# wireless-dong-mk-2_2.net
KiCad netlist of a schematic drawn in EAGLE
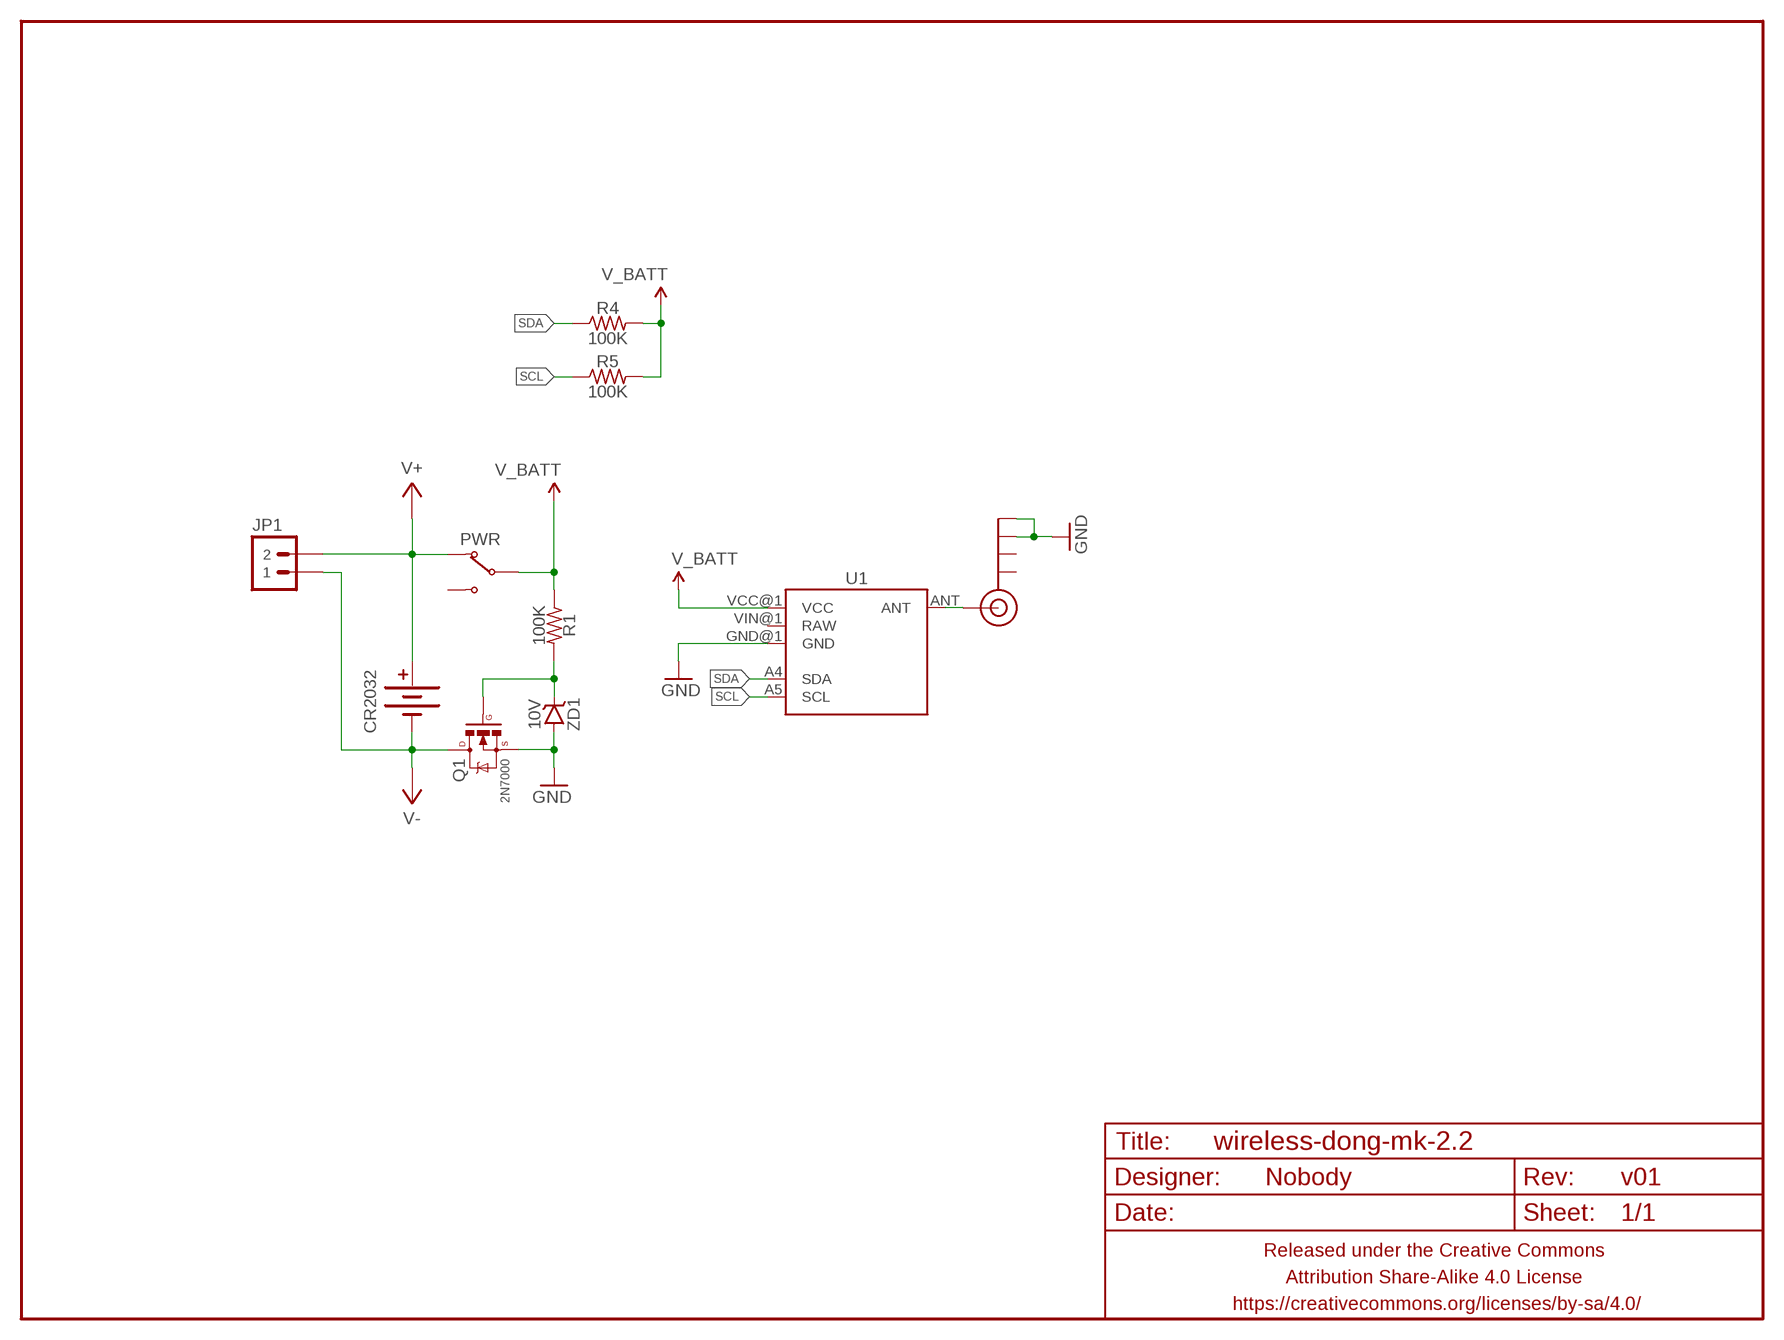
[diagram p0: schematic, sheet 1]

(export (version "E")
  (design (tool "Eeschema 10.0.6"))
  (components
    (comp (ref "ANT")
      (value "SMA_EDGE")
      (footprint "eagle-import:SMA-EDGE")
      (libsource (lib "eagle-import") (part "SMA_EDGE"))
    )
    (comp (ref "CR2032")
      (value "BATTERY20PTH_TOPLOAD")
      (footprint "eagle-import:BATTCON_20MM_PTH_TOPLOAD")
      (libsource (lib "eagle-import") (part "BATTERY20PTH_TOPLOAD"))
    )
    (comp (ref "FRAME1")
      (value "FRAME-LETTERNO_PACKAGE")
      (footprint "eagle-import:DUMMY")
      (fields (field (name "DESIGNER") "Nobody"))
      (libsource (lib "eagle-import") (part "FRAME-LETTERNO_PACKAGE"))
    )
    (comp (ref "JP1")
      (value "M02PTH-CENTERED-R+")
      (footprint "eagle-import:1X02-CENTER-R+")
      (libsource (lib "eagle-import") (part "M02PTH-CENTERED-R+"))
    )
    (comp (ref "PWR")
      (value "SWITCH-SPDTPTH-RA-2.54MM")
      (footprint "eagle-import:SPDT-RA-2.54MM")
      (libsource (lib "eagle-import") (part "SWITCH-SPDTPTH-RA-2.54MM"))
    )
    (comp (ref "Q1")
      (value "2N7000")
      (footprint "eagle-import:TO-92-AMMO")
      (libsource (lib "eagle-import") (part "MOSFET-NCHANNEL2N7000-AMMO"))
    )
    (comp (ref "R1")
      (value "100K")
      (footprint "eagle-import:RESISTOR-AXIAL-PTH-7.62MM")
      (libsource (lib "eagle-import") (part "RESISTORPTH-AXIAL-7.62MM"))
    )
    (comp (ref "R4")
      (value "100K")
      (footprint "eagle-import:RESISTOR-AXIAL-PTH-7.62MM")
      (libsource (lib "eagle-import") (part "RESISTORPTH-AXIAL-7.62MM"))
    )
    (comp (ref "R5")
      (value "100K")
      (footprint "eagle-import:RESISTOR-AXIAL-PTH-7.62MM")
      (libsource (lib "eagle-import") (part "RESISTORPTH-AXIAL-7.62MM"))
    )
    (comp (ref "U1")
      (value "MOTEINO_BOAT")
      (footprint "eagle-import:MOTEINO_BOAT")
      (libsource (lib "eagle-import") (part "MOTEINO_BOAT"))
    )
    (comp (ref "ZD1")
      (value "10V")
      (footprint "eagle-import:DIODE-ZENNER-7.62MM")
      (libsource (lib "eagle-import") (part "DIODE-ZENER7.62MM-PTH"))
    )
  )
  (nets
    (net (code "1") (name "GND") (class "Default")
      (node (ref "ANT") (pin "GND@2") (pinfunction "GND_GND@2") (pintype "bidirectional"))
      (node (ref "ANT") (pin "GND@3") (pinfunction "GND_GND@3") (pintype "bidirectional"))
      (node (ref "Q1") (pin "1") (pinfunction "S_1") (pintype "passive"))
      (node (ref "U1") (pin "GND@1") (pinfunction "GND_GND@1") (pintype "bidirectional"))
      (node (ref "ZD1") (pin "A") (pinfunction "A_A") (pintype "passive"))
    )
    (net (code "2") (name "Net-(ANT-SIGNAL)") (class "Default")
      (node (ref "ANT") (pin "SIG") (pinfunction "SIGNAL_SIG") (pintype "bidirectional"))
      (node (ref "U1") (pin "ANT") (pinfunction "ANT_ANT") (pintype "bidirectional"))
    )
    (net (code "3") (name "Net-(Q1-G)") (class "Default")
      (node (ref "Q1") (pin "2") (pinfunction "G_2") (pintype "passive"))
      (node (ref "R1") (pin "P$2") (pinfunction "2_P$2") (pintype "passive"))
      (node (ref "ZD1") (pin "K") (pinfunction "C_K") (pintype "passive"))
    )
    (net (code "4") (name "SCL") (class "Default")
      (node (ref "R5") (pin "P$1") (pinfunction "1_P$1") (pintype "passive"))
      (node (ref "U1") (pin "A5") (pinfunction "SCL_A5") (pintype "bidirectional"))
    )
    (net (code "5") (name "SDA") (class "Default")
      (node (ref "R4") (pin "P$1") (pinfunction "1_P$1") (pintype "passive"))
      (node (ref "U1") (pin "A4") (pinfunction "SDA_A4") (pintype "bidirectional"))
    )
    (net (code "6") (name "V+") (class "Default")
      (node (ref "CR2032") (pin "+") (pinfunction "+_+") (pintype "power_in"))
      (node (ref "JP1") (pin "2") (pinfunction "2_2") (pintype "passive"))
      (node (ref "PWR") (pin "1") (pinfunction "NC_1") (pintype "passive"))
    )
    (net (code "7") (name "V-") (class "Default")
      (node (ref "CR2032") (pin "-") (pinfunction "-_-") (pintype "power_in"))
      (node (ref "JP1") (pin "1") (pinfunction "1_1") (pintype "passive"))
      (node (ref "Q1") (pin "3") (pinfunction "D_3") (pintype "passive"))
    )
    (net (code "8") (name "V_BATT") (class "Default")
      (node (ref "PWR") (pin "2") (pinfunction "COM_2") (pintype "passive"))
      (node (ref "R1") (pin "P$1") (pinfunction "1_P$1") (pintype "passive"))
      (node (ref "R4") (pin "P$2") (pinfunction "2_P$2") (pintype "passive"))
      (node (ref "R5") (pin "P$2") (pinfunction "2_P$2") (pintype "passive"))
      (node (ref "U1") (pin "VCC@1") (pinfunction "VCC_VCC@1") (pintype "bidirectional"))
    )
    (net (code "9") (name "unconnected-(ANT-GND-PadGND@0)") (class "Default")
      (node (ref "ANT") (pin "GND@0") (pinfunction "GND_GND@0") (pintype "bidirectional"))
    )
    (net (code "10") (name "unconnected-(ANT-GND-PadGND@1)") (class "Default")
      (node (ref "ANT") (pin "GND@1") (pinfunction "GND_GND@1") (pintype "bidirectional"))
    )
    (net (code "11") (name "unconnected-(PWR-NO-Pad3)") (class "Default")
      (node (ref "PWR") (pin "3") (pinfunction "NO_3") (pintype "passive"))
    )
    (net (code "12") (name "unconnected-(U1-RAW-PadVIN@1)") (class "Default")
      (node (ref "U1") (pin "VIN@1") (pinfunction "RAW_VIN@1") (pintype "bidirectional"))
    )
  )
)
